# arduino-pro-mini_2-way-switches_v0_2_5_S.net
KiCad netlist of a schematic drawn in EAGLE
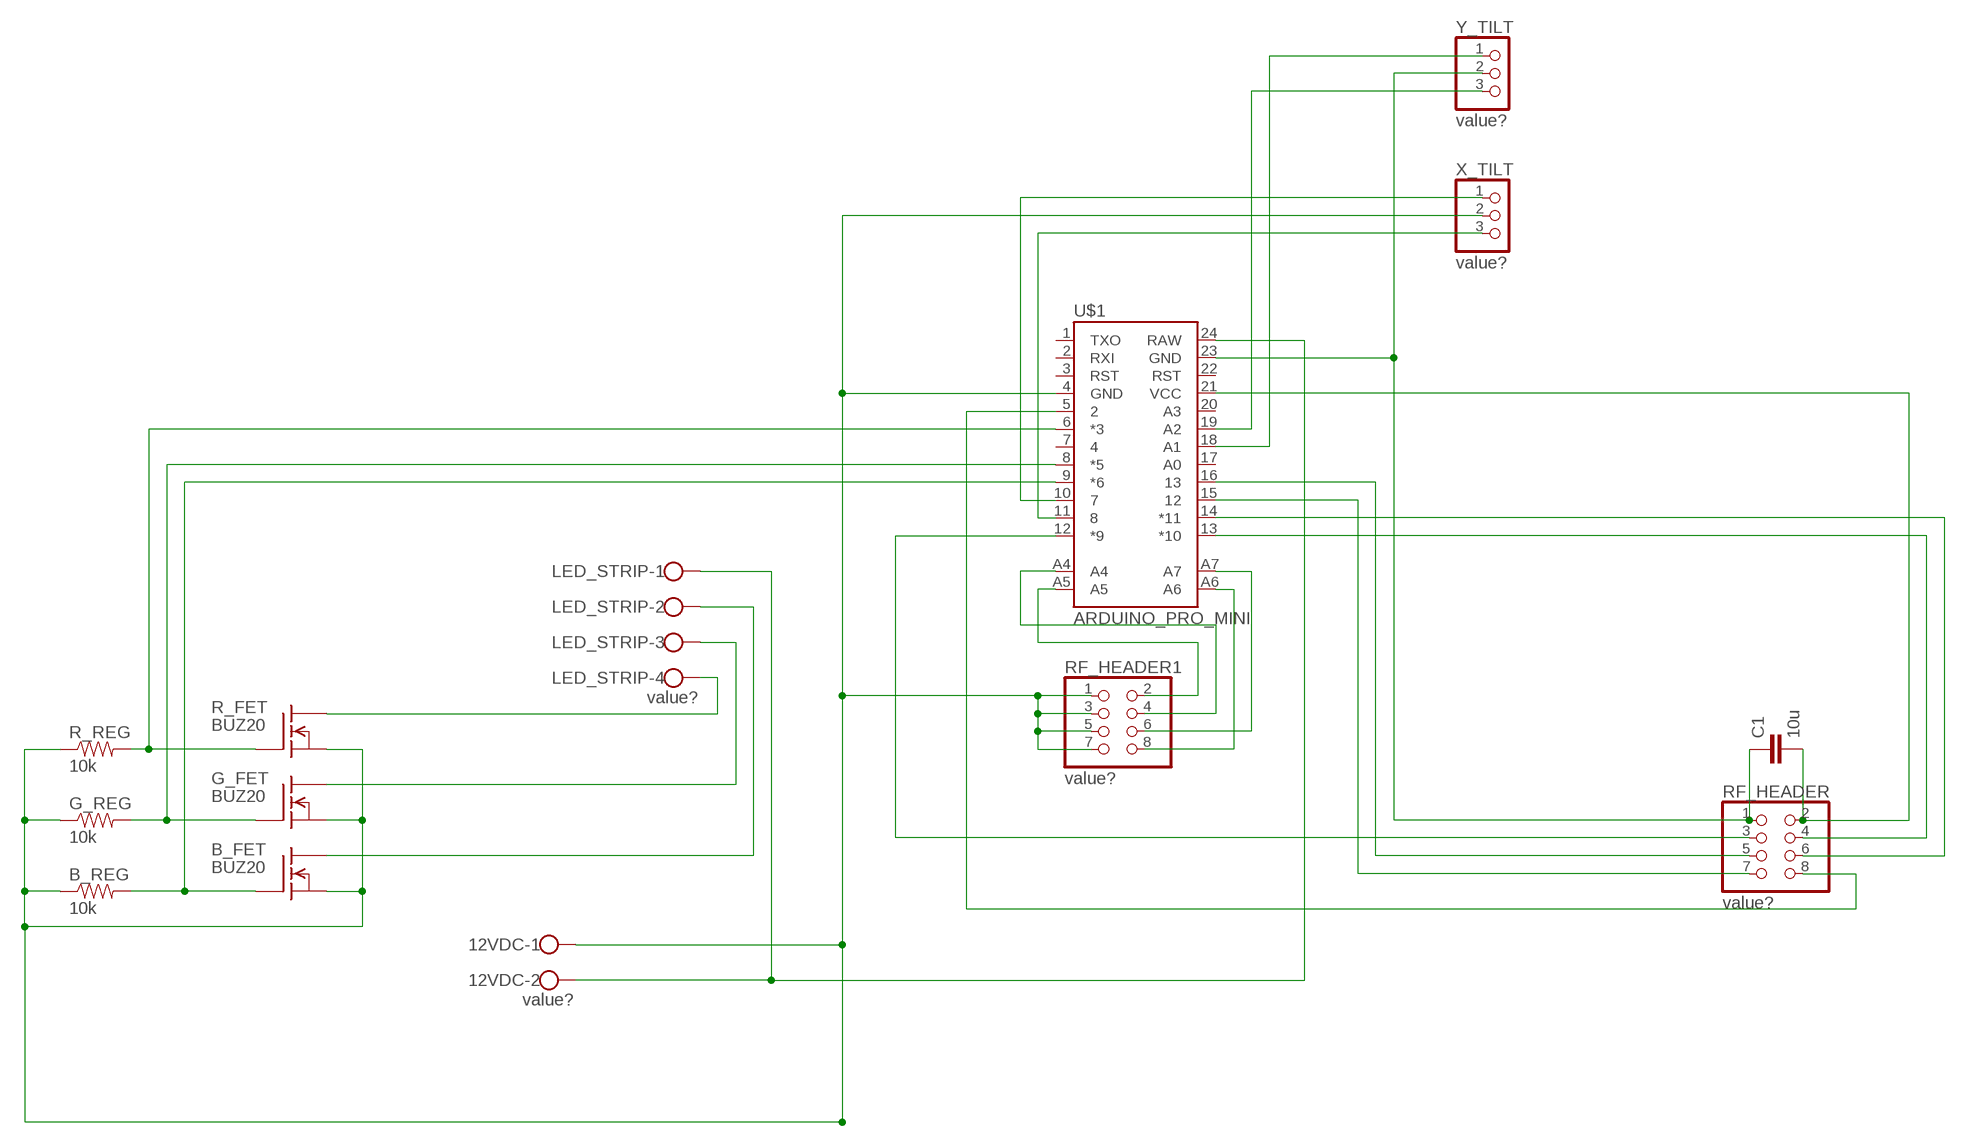
[diagram p0: schematic, sheet 1]

(export (version "E")
  (design (tool "Eeschema 10.0.6"))
  (components
    (comp (ref "12VDC")
      (value "value?")
      (footprint "eagle-import:W237-102")
      (fields (field (name "MPN") "237-102"))
      (libsource (lib "eagle-import") (part "W237-102"))
    )
    (comp (ref "B_FET")
      (value "BUZ20")
      (footprint "eagle-import:TO220")
      (libsource (lib "eagle-import") (part "BUZ20"))
    )
    (comp (ref "B_REG")
      (value "10k")
      (footprint "eagle-import:AXIAL-0.4")
      (libsource (lib "eagle-import") (part "RESISTORPTH-1/4W"))
    )
    (comp (ref "C1")
      (value "10u")
      (footprint "eagle-import:CAP-PTH-SMALL")
      (libsource (lib "eagle-import") (part "CAPPTH"))
    )
    (comp (ref "G_FET")
      (value "BUZ20")
      (footprint "eagle-import:TO220")
      (libsource (lib "eagle-import") (part "BUZ20"))
    )
    (comp (ref "G_REG")
      (value "10k")
      (footprint "eagle-import:AXIAL-0.4")
      (libsource (lib "eagle-import") (part "RESISTORPTH-1/4W"))
    )
    (comp (ref "LED_STRIP")
      (value "value?")
      (footprint "eagle-import:W237-4")
      (libsource (lib "eagle-import") (part "W237-4"))
    )
    (comp (ref "RF_HEADER")
      (value "value?")
      (footprint "eagle-import:2X04")
      (libsource (lib "eagle-import") (part "PINHD-2X4"))
    )
    (comp (ref "RF_HEADER1")
      (value "value?")
      (footprint "eagle-import:2X04")
      (libsource (lib "eagle-import") (part "PINHD-2X4"))
    )
    (comp (ref "R_FET")
      (value "BUZ20")
      (footprint "eagle-import:TO220")
      (libsource (lib "eagle-import") (part "BUZ20"))
    )
    (comp (ref "R_REG")
      (value "10k")
      (footprint "eagle-import:AXIAL-0.4")
      (libsource (lib "eagle-import") (part "RESISTORPTH-1/4W"))
    )
    (comp (ref "U$1")
      (value "ARDUINO_PRO_MINI")
      (footprint "eagle-import:ARDUINO_PRO_MINI")
      (libsource (lib "eagle-import") (part "ARDUINO_PRO_MINI"))
    )
    (comp (ref "X_TILT")
      (value "value?")
      (footprint "eagle-import:1X03")
      (libsource (lib "eagle-import") (part "PINHD-1X3"))
    )
    (comp (ref "Y_TILT")
      (value "value?")
      (footprint "eagle-import:1X03")
      (libsource (lib "eagle-import") (part "PINHD-1X3"))
    )
  )
  (nets
    (net (code "1") (name "Net-(12VDCA-KL)") (class "Default")
      (node (ref "12VDC") (pin "1") (pinfunction "KL_1") (pintype "passive"))
      (node (ref "B_FET") (pin "3") (pinfunction "S_3") (pintype "passive"))
      (node (ref "B_REG") (pin "P$1") (pinfunction "1_P$1") (pintype "passive"))
      (node (ref "G_FET") (pin "3") (pinfunction "S_3") (pintype "passive"))
      (node (ref "G_REG") (pin "P$1") (pinfunction "1_P$1") (pintype "passive"))
      (node (ref "RF_HEADER1") (pin "1") (pinfunction "1_1") (pintype "passive"))
      (node (ref "RF_HEADER1") (pin "3") (pinfunction "3_3") (pintype "passive"))
      (node (ref "RF_HEADER1") (pin "5") (pinfunction "5_5") (pintype "passive"))
      (node (ref "RF_HEADER1") (pin "7") (pinfunction "7_7") (pintype "passive"))
      (node (ref "R_FET") (pin "3") (pinfunction "S_3") (pintype "passive"))
      (node (ref "R_REG") (pin "P$1") (pinfunction "1_P$1") (pintype "passive"))
      (node (ref "U$1") (pin "4") (pinfunction "GND_4") (pintype "bidirectional"))
      (node (ref "X_TILT") (pin "2") (pinfunction "2_2") (pintype "passive"))
    )
    (net (code "2") (name "Net-(12VDCB-KL)") (class "Default")
      (node (ref "12VDC") (pin "2") (pinfunction "KL_2") (pintype "passive"))
      (node (ref "LED_STRIP") (pin "1") (pinfunction "KL_1") (pintype "passive"))
      (node (ref "U$1") (pin "24") (pinfunction "RAW_24") (pintype "bidirectional"))
    )
    (net (code "3") (name "Net-(B_FET-D)") (class "Default")
      (node (ref "B_FET") (pin "2") (pinfunction "D_2") (pintype "passive"))
      (node (ref "LED_STRIP") (pin "2") (pinfunction "KL_2") (pintype "passive"))
    )
    (net (code "4") (name "Net-(B_FET-G)") (class "Default")
      (node (ref "B_FET") (pin "1") (pinfunction "G_1") (pintype "passive"))
      (node (ref "B_REG") (pin "P$2") (pinfunction "2_P$2") (pintype "passive"))
      (node (ref "U$1") (pin "9") (pinfunction "*6_9") (pintype "bidirectional"))
    )
    (net (code "5") (name "Net-(C1-Pad1)") (class "Default")
      (node (ref "C1") (pin "1") (pinfunction "1_1") (pintype "passive"))
      (node (ref "RF_HEADER") (pin "1") (pinfunction "1_1") (pintype "passive"))
      (node (ref "U$1") (pin "23") (pinfunction "GND_23") (pintype "bidirectional"))
      (node (ref "Y_TILT") (pin "2") (pinfunction "2_2") (pintype "passive"))
    )
    (net (code "6") (name "Net-(G_FET-D)") (class "Default")
      (node (ref "G_FET") (pin "2") (pinfunction "D_2") (pintype "passive"))
      (node (ref "LED_STRIP") (pin "3") (pinfunction "KL_3") (pintype "passive"))
    )
    (net (code "7") (name "Net-(G_FET-G)") (class "Default")
      (node (ref "G_FET") (pin "1") (pinfunction "G_1") (pintype "passive"))
      (node (ref "G_REG") (pin "P$2") (pinfunction "2_P$2") (pintype "passive"))
      (node (ref "U$1") (pin "8") (pinfunction "*5_8") (pintype "bidirectional"))
    )
    (net (code "8") (name "Net-(LED_STRIPD-KL)") (class "Default")
      (node (ref "LED_STRIP") (pin "4") (pinfunction "KL_4") (pintype "passive"))
      (node (ref "R_FET") (pin "2") (pinfunction "D_2") (pintype "passive"))
    )
    (net (code "9") (name "Net-(RF_HEADER1-Pad2)") (class "Default")
      (node (ref "RF_HEADER1") (pin "2") (pinfunction "2_2") (pintype "passive"))
      (node (ref "U$1") (pin "A5") (pinfunction "A5_A5") (pintype "bidirectional"))
    )
    (net (code "10") (name "Net-(RF_HEADER1-Pad4)") (class "Default")
      (node (ref "RF_HEADER1") (pin "4") (pinfunction "4_4") (pintype "passive"))
      (node (ref "U$1") (pin "A4") (pinfunction "A4_A4") (pintype "bidirectional"))
    )
    (net (code "11") (name "Net-(RF_HEADER1-Pad6)") (class "Default")
      (node (ref "RF_HEADER1") (pin "6") (pinfunction "6_6") (pintype "passive"))
      (node (ref "U$1") (pin "A7") (pinfunction "A7_A7") (pintype "bidirectional"))
    )
    (net (code "12") (name "Net-(RF_HEADER1-Pad8)") (class "Default")
      (node (ref "RF_HEADER1") (pin "8") (pinfunction "8_8") (pintype "passive"))
      (node (ref "U$1") (pin "A6") (pinfunction "A6_A6") (pintype "bidirectional"))
    )
    (net (code "13") (name "Net-(R_FET-G)") (class "Default")
      (node (ref "R_FET") (pin "1") (pinfunction "G_1") (pintype "passive"))
      (node (ref "R_REG") (pin "P$2") (pinfunction "2_P$2") (pintype "passive"))
      (node (ref "U$1") (pin "6") (pinfunction "*3_6") (pintype "bidirectional"))
    )
    (net (code "14") (name "Net-(U$1-*9)") (class "Default")
      (node (ref "RF_HEADER") (pin "3") (pinfunction "3_3") (pintype "passive"))
      (node (ref "U$1") (pin "12") (pinfunction "*9_12") (pintype "bidirectional"))
    )
    (net (code "15") (name "Net-(U$1-*10)") (class "Default")
      (node (ref "RF_HEADER") (pin "4") (pinfunction "4_4") (pintype "passive"))
      (node (ref "U$1") (pin "13") (pinfunction "*10_13") (pintype "bidirectional"))
    )
    (net (code "16") (name "Net-(U$1-*11)") (class "Default")
      (node (ref "RF_HEADER") (pin "6") (pinfunction "6_6") (pintype "passive"))
      (node (ref "U$1") (pin "14") (pinfunction "*11_14") (pintype "bidirectional"))
    )
    (net (code "17") (name "Net-(U$1-2)") (class "Default")
      (node (ref "RF_HEADER") (pin "8") (pinfunction "8_8") (pintype "passive"))
      (node (ref "U$1") (pin "5") (pinfunction "2_5") (pintype "bidirectional"))
    )
    (net (code "18") (name "Net-(U$1-7)") (class "Default")
      (node (ref "U$1") (pin "10") (pinfunction "7_10") (pintype "bidirectional"))
      (node (ref "X_TILT") (pin "1") (pinfunction "1_1") (pintype "passive"))
    )
    (net (code "19") (name "Net-(U$1-8)") (class "Default")
      (node (ref "U$1") (pin "11") (pinfunction "8_11") (pintype "bidirectional"))
      (node (ref "X_TILT") (pin "3") (pinfunction "3_3") (pintype "passive"))
    )
    (net (code "20") (name "Net-(U$1-12)") (class "Default")
      (node (ref "RF_HEADER") (pin "7") (pinfunction "7_7") (pintype "passive"))
      (node (ref "U$1") (pin "15") (pinfunction "12_15") (pintype "bidirectional"))
    )
    (net (code "21") (name "Net-(U$1-13)") (class "Default")
      (node (ref "RF_HEADER") (pin "5") (pinfunction "5_5") (pintype "passive"))
      (node (ref "U$1") (pin "16") (pinfunction "13_16") (pintype "bidirectional"))
    )
    (net (code "22") (name "Net-(U$1-A1)") (class "Default")
      (node (ref "U$1") (pin "18") (pinfunction "A1_18") (pintype "bidirectional"))
      (node (ref "Y_TILT") (pin "1") (pinfunction "1_1") (pintype "passive"))
    )
    (net (code "23") (name "Net-(U$1-A2)") (class "Default")
      (node (ref "U$1") (pin "19") (pinfunction "A2_19") (pintype "bidirectional"))
      (node (ref "Y_TILT") (pin "3") (pinfunction "3_3") (pintype "passive"))
    )
    (net (code "24") (name "Net-(U$1-VCC)") (class "Default")
      (node (ref "C1") (pin "2") (pinfunction "2_2") (pintype "passive"))
      (node (ref "RF_HEADER") (pin "2") (pinfunction "2_2") (pintype "passive"))
      (node (ref "U$1") (pin "21") (pinfunction "VCC_21") (pintype "bidirectional"))
    )
    (net (code "25") (name "unconnected-(U$1-4-Pad7)") (class "Default")
      (node (ref "U$1") (pin "7") (pinfunction "4_7") (pintype "bidirectional"))
    )
    (net (code "26") (name "unconnected-(U$1-A0-Pad17)") (class "Default")
      (node (ref "U$1") (pin "17") (pinfunction "A0_17") (pintype "bidirectional"))
    )
    (net (code "27") (name "unconnected-(U$1-A3-Pad20)") (class "Default")
      (node (ref "U$1") (pin "20") (pinfunction "A3_20") (pintype "bidirectional"))
    )
    (net (code "28") (name "unconnected-(U$1-RST-Pad3)") (class "Default")
      (node (ref "U$1") (pin "3") (pinfunction "RST_3") (pintype "bidirectional"))
    )
    (net (code "29") (name "unconnected-(U$1-RST-Pad22)") (class "Default")
      (node (ref "U$1") (pin "22") (pinfunction "RST_22") (pintype "bidirectional"))
    )
    (net (code "30") (name "unconnected-(U$1-RXI-Pad2)") (class "Default")
      (node (ref "U$1") (pin "2") (pinfunction "RXI_2") (pintype "bidirectional"))
    )
    (net (code "31") (name "unconnected-(U$1-TXO-Pad1)") (class "Default")
      (node (ref "U$1") (pin "1") (pinfunction "TXO_1") (pintype "bidirectional"))
    )
  )
)
